# OPAMP_DEV_SOT5_6-23.net
KiCad netlist of a schematic drawn in Altium Designer
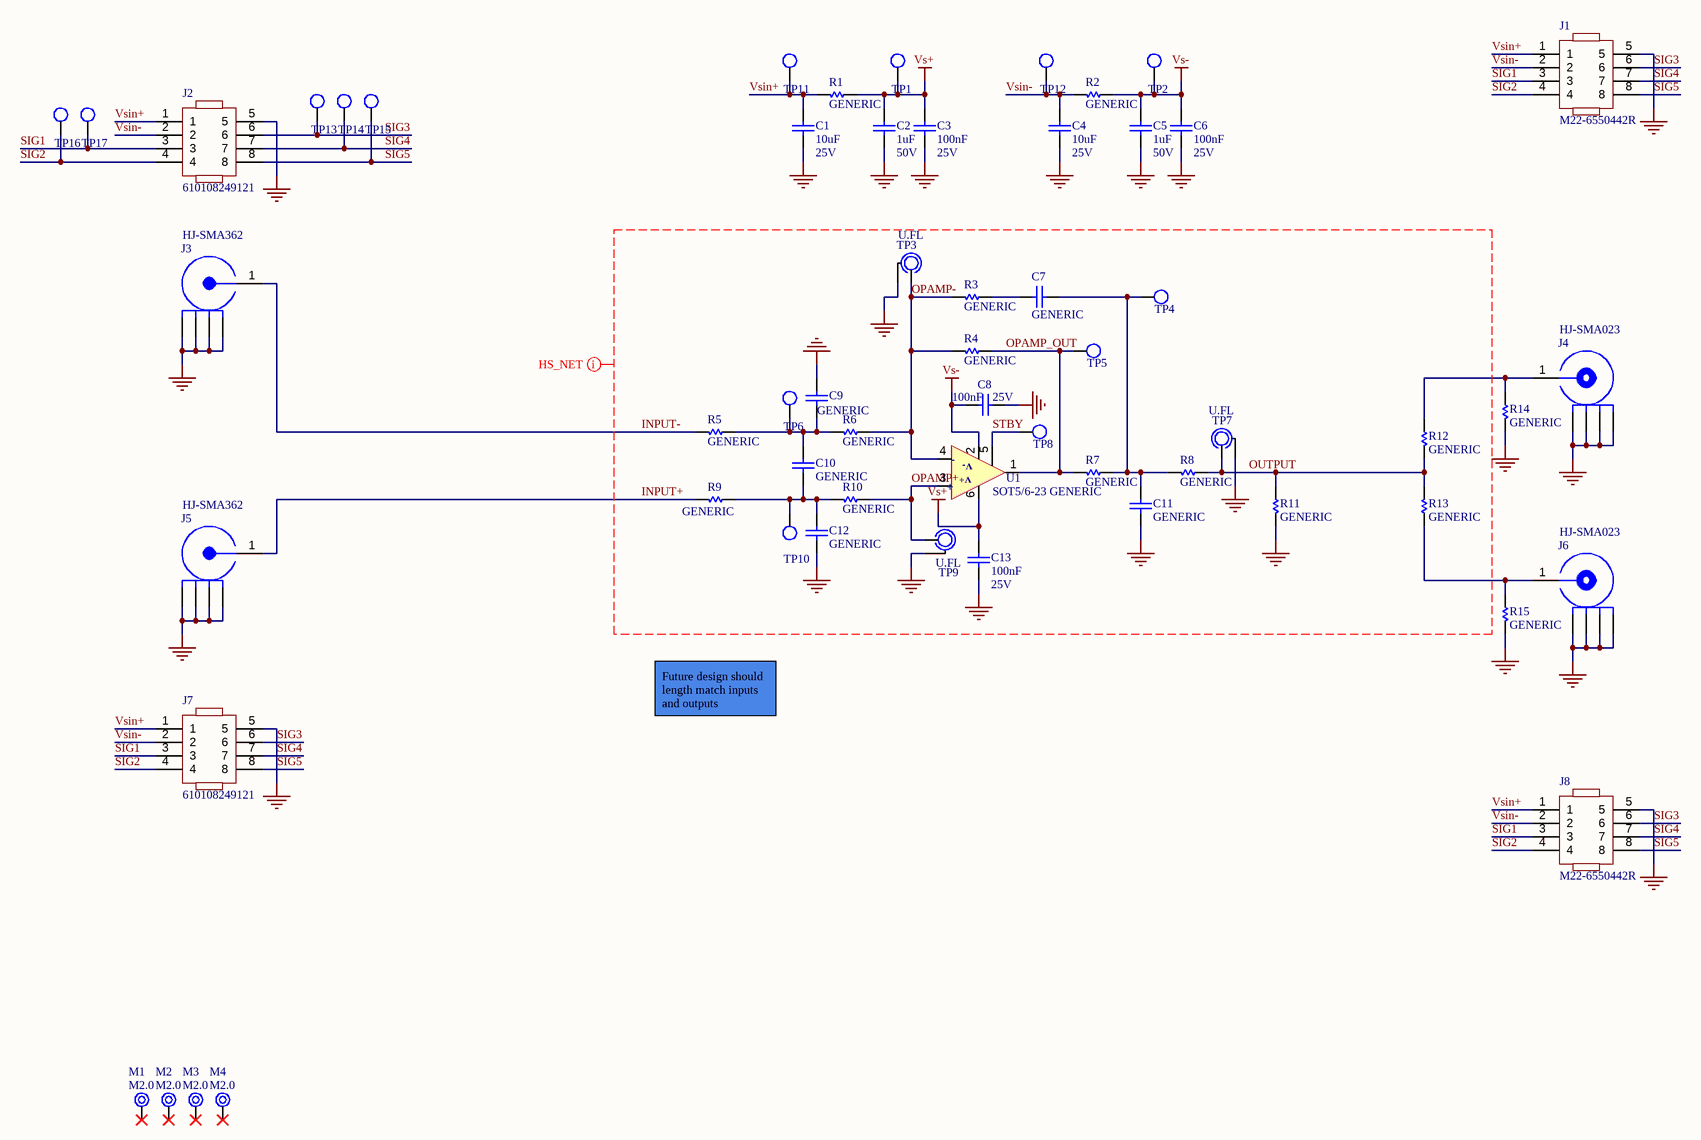
[diagram p0: OPAMP_DEV_SOT5_6-23.SchDoc]

(export (version "E")
  (design (tool "Eeschema 10.0.6"))
  (components
    (comp (ref "C1")
      (value "10uF")
      (footprint "c0805")
      (description "Cap Ceramic 10uF 25V X5R 10% SMD 0805 85°C Embossed T/R")
      (fields
        (field (name "MANUFACTURER") "Samsung")
        (field (name "MANUFACTURER PART NUMBER") "CL21A106KAYNNNE")
        (field (name "VOLTAGE RATING") "25V")
      )
      (libsource (lib "OPAMP_DEV_SOT5_6-23") (part "CAP CER 10uF 25V X5R 0805"))
    )
    (comp (ref "C2")
      (value "1uF")
      (footprint "c0603")
      (description "Multilayer Ceramic Capacitors (High dielectric type), 50V, 1 uF, ± 10 %, 0603, X5R, RoHS")
      (fields
        (field (name "MANUFACTURER") "Taiyo Yuden")
        (field (name "MANUFACTURER PART NUMBER") "UMK107BJ105KA-T")
        (field (name "VOLTAGE RATING") "50V")
      )
      (libsource (lib "OPAMP_DEV_SOT5_6-23") (part "CAP CER 1uF 50V X5R 0603"))
    )
    (comp (ref "C3")
      (value "100nF")
      (footprint "C0402")
      (description "Cap Ceramic 0.1uF 25V X5R 10% Pad SMD 0402 85°C T/R / Multi Layer Ceramic Capacitor (MLCC)")
      (fields
        (field (name "MANUFACTURER") "Samsung")
        (field (name "MANUFACTURER PART NUMBER") "CL05A104KA5NNNC")
        (field (name "VOLTAGE RATING") "25V")
      )
      (libsource (lib "OPAMP_DEV_SOT5_6-23") (part "CAP CER 100nF 25V X5R 0402"))
    )
    (comp (ref "C4")
      (value "10uF")
      (footprint "c0805")
      (description "Cap Ceramic 10uF 25V X5R 10% SMD 0805 85°C Embossed T/R")
      (fields
        (field (name "MANUFACTURER") "Samsung")
        (field (name "MANUFACTURER PART NUMBER") "CL21A106KAYNNNE")
        (field (name "VOLTAGE RATING") "25V")
      )
      (libsource (lib "OPAMP_DEV_SOT5_6-23") (part "CAP CER 10uF 25V X5R 0805"))
    )
    (comp (ref "C5")
      (value "1uF")
      (footprint "c0603")
      (description "Multilayer Ceramic Capacitors (High dielectric type), 50V, 1 uF, ± 10 %, 0603, X5R, RoHS")
      (fields
        (field (name "MANUFACTURER") "Taiyo Yuden")
        (field (name "MANUFACTURER PART NUMBER") "UMK107BJ105KA-T")
        (field (name "VOLTAGE RATING") "50V")
      )
      (libsource (lib "OPAMP_DEV_SOT5_6-23") (part "CAP CER 1uF 50V X5R 0603"))
    )
    (comp (ref "C6")
      (value "100nF")
      (footprint "C0402")
      (description "Cap Ceramic 0.1uF 25V X5R 10% Pad SMD 0402 85°C T/R / Multi Layer Ceramic Capacitor (MLCC)")
      (fields
        (field (name "MANUFACTURER") "Samsung")
        (field (name "MANUFACTURER PART NUMBER") "CL05A104KA5NNNC")
        (field (name "VOLTAGE RATING") "25V")
      )
      (libsource (lib "OPAMP_DEV_SOT5_6-23") (part "CAP CER 100nF 25V X5R 0402"))
    )
    (comp (ref "C7")
      (value "GENERIC")
      (footprint "C0402")
      (libsource (lib "OPAMP_DEV_SOT5_6-23") (part "CAP GENERIC 0402"))
    )
    (comp (ref "C8")
      (value "100nF")
      (footprint "C0402")
      (description "Cap Ceramic 0.1uF 25V X5R 10% Pad SMD 0402 85°C T/R / Multi Layer Ceramic Capacitor (MLCC)")
      (fields
        (field (name "MANUFACTURER") "Samsung")
        (field (name "MANUFACTURER PART NUMBER") "CL05A104KA5NNNC")
        (field (name "VOLTAGE RATING") "25V")
      )
      (libsource (lib "OPAMP_DEV_SOT5_6-23") (part "CAP CER 100nF 25V X5R 0402"))
    )
    (comp (ref "C9")
      (value "GENERIC")
      (footprint "C0402")
      (libsource (lib "OPAMP_DEV_SOT5_6-23") (part "CAP GENERIC 0402"))
    )
    (comp (ref "C10")
      (value "GENERIC")
      (footprint "C0402")
      (libsource (lib "OPAMP_DEV_SOT5_6-23") (part "CAP GENERIC 0402"))
    )
    (comp (ref "C11")
      (value "GENERIC")
      (footprint "C0402")
      (libsource (lib "OPAMP_DEV_SOT5_6-23") (part "CAP GENERIC 0402"))
    )
    (comp (ref "C12")
      (value "GENERIC")
      (footprint "C0402")
      (libsource (lib "OPAMP_DEV_SOT5_6-23") (part "CAP GENERIC 0402"))
    )
    (comp (ref "C13")
      (value "100nF")
      (footprint "C0402")
      (description "Cap Ceramic 0.1uF 25V X5R 10% Pad SMD 0402 85°C T/R / Multi Layer Ceramic Capacitor (MLCC)")
      (fields
        (field (name "MANUFACTURER") "Samsung")
        (field (name "MANUFACTURER PART NUMBER") "CL05A104KA5NNNC")
        (field (name "VOLTAGE RATING") "25V")
      )
      (libsource (lib "OPAMP_DEV_SOT5_6-23") (part "CAP CER 100nF 25V X5R 0402"))
    )
    (comp (ref "J1")
      (value "M22-6550442R")
      (footprint "CONN HDR 08 FEMALE RA 2ROW")
      (description "Conn Socket Strip RCP 8 POS 2mm Solder RA SMD T/R")
      (fields (field (name "MANUFACTURER") "Harwin"))
      (libsource (lib "OPAMP_DEV_SOT5_6-23") (part "CONN HDR 08 FEMALE RA 2 ROW"))
    )
    (comp (ref "J2")
      (value "610108249121")
      (footprint "CONN HDR 08 MALE RA 2ROW - duplicate")
      (description "SMT Angled Pin Header WR-PHD, Pitch 2.54 mm, Dual Row, 8 pins")
      (fields (field (name "MANUFACTURER") "Wurth Electronics"))
      (libsource (lib "OPAMP_DEV_SOT5_6-23") (part "CONN HDR 08 MALE RA 2 ROW"))
    )
    (comp (ref "J3")
      (value "HJ-SMA362")
      (footprint "SMA SMD PIN BRD EDGE")
      (libsource (lib "OPAMP_DEV_SOT5_6-23") (part "CON SMA PIN SMD BRD EDGE HJ-SMA362"))
    )
    (comp (ref "J4")
      (value "HJ-SMA023")
      (footprint "SMA SMD BORE BRD EDGE")
      (libsource (lib "OPAMP_DEV_SOT5_6-23") (part "CON SMA BORE SMD BRD EDGE HJ-SMA023"))
    )
    (comp (ref "J5")
      (value "HJ-SMA362")
      (footprint "SMA SMD PIN BRD EDGE")
      (libsource (lib "OPAMP_DEV_SOT5_6-23") (part "CON SMA PIN SMD BRD EDGE HJ-SMA362"))
    )
    (comp (ref "J6")
      (value "HJ-SMA023")
      (footprint "SMA SMD BORE BRD EDGE")
      (libsource (lib "OPAMP_DEV_SOT5_6-23") (part "CON SMA BORE SMD BRD EDGE HJ-SMA023"))
    )
    (comp (ref "J7")
      (value "610108249121")
      (footprint "CONN HDR 08 MALE RA 2ROW - duplicate")
      (description "SMT Angled Pin Header WR-PHD, Pitch 2.54 mm, Dual Row, 8 pins")
      (fields (field (name "MANUFACTURER") "Wurth Electronics"))
      (libsource (lib "OPAMP_DEV_SOT5_6-23") (part "CONN HDR 08 MALE RA 2 ROW"))
    )
    (comp (ref "J8")
      (value "M22-6550442R")
      (footprint "CONN HDR 08 FEMALE RA 2ROW")
      (description "Conn Socket Strip RCP 8 POS 2mm Solder RA SMD T/R")
      (fields (field (name "MANUFACTURER") "Harwin"))
      (libsource (lib "OPAMP_DEV_SOT5_6-23") (part "CONN HDR 08 FEMALE RA 2 ROW"))
    )
    (comp (ref "M1")
      (value "M2.0")
      (footprint "MECH M2.0 UNPLATED")
      (libsource (lib "OPAMP_DEV_SOT5_6-23") (part "MECH M2.0 UNPLATED"))
    )
    (comp (ref "M2")
      (value "M2.0")
      (footprint "MECH M2.0 UNPLATED")
      (libsource (lib "OPAMP_DEV_SOT5_6-23") (part "MECH M2.0 UNPLATED"))
    )
    (comp (ref "M3")
      (value "M2.0")
      (footprint "MECH M2.0 UNPLATED")
      (libsource (lib "OPAMP_DEV_SOT5_6-23") (part "MECH M2.0 UNPLATED"))
    )
    (comp (ref "M4")
      (value "M2.0")
      (footprint "MECH M2.0 UNPLATED")
      (libsource (lib "OPAMP_DEV_SOT5_6-23") (part "MECH M2.0 UNPLATED"))
    )
    (comp (ref "R1")
      (value "GENERIC")
      (footprint "R0603")
      (libsource (lib "OPAMP_DEV_SOT5_6-23") (part "RES GENERIC 0603"))
    )
    (comp (ref "R2")
      (value "GENERIC")
      (footprint "R0603")
      (libsource (lib "OPAMP_DEV_SOT5_6-23") (part "RES GENERIC 0603"))
    )
    (comp (ref "R3")
      (value "GENERIC")
      (footprint "R0402")
      (libsource (lib "OPAMP_DEV_SOT5_6-23") (part "RES GENERIC 0402"))
    )
    (comp (ref "R4")
      (value "GENERIC")
      (footprint "R0402")
      (libsource (lib "OPAMP_DEV_SOT5_6-23") (part "RES GENERIC 0402"))
    )
    (comp (ref "R5")
      (value "GENERIC")
      (footprint "R0402")
      (libsource (lib "OPAMP_DEV_SOT5_6-23") (part "RES GENERIC 0402"))
    )
    (comp (ref "R6")
      (value "GENERIC")
      (footprint "R0402")
      (libsource (lib "OPAMP_DEV_SOT5_6-23") (part "RES GENERIC 0402"))
    )
    (comp (ref "R7")
      (value "GENERIC")
      (footprint "R0402")
      (libsource (lib "OPAMP_DEV_SOT5_6-23") (part "RES GENERIC 0402"))
    )
    (comp (ref "R8")
      (value "GENERIC")
      (footprint "R0402")
      (libsource (lib "OPAMP_DEV_SOT5_6-23") (part "RES GENERIC 0402"))
    )
    (comp (ref "R9")
      (value "GENERIC")
      (footprint "R0402")
      (libsource (lib "OPAMP_DEV_SOT5_6-23") (part "RES GENERIC 0402"))
    )
    (comp (ref "R10")
      (value "GENERIC")
      (footprint "R0402")
      (libsource (lib "OPAMP_DEV_SOT5_6-23") (part "RES GENERIC 0402"))
    )
    (comp (ref "R11")
      (value "GENERIC")
      (footprint "R0402")
      (libsource (lib "OPAMP_DEV_SOT5_6-23") (part "RES GENERIC 0402"))
    )
    (comp (ref "R12")
      (value "GENERIC")
      (footprint "R0402")
      (libsource (lib "OPAMP_DEV_SOT5_6-23") (part "RES GENERIC 0402"))
    )
    (comp (ref "R13")
      (value "GENERIC")
      (footprint "R0402")
      (libsource (lib "OPAMP_DEV_SOT5_6-23") (part "RES GENERIC 0402"))
    )
    (comp (ref "R14")
      (value "GENERIC")
      (footprint "R0402")
      (libsource (lib "OPAMP_DEV_SOT5_6-23") (part "RES GENERIC 0402"))
    )
    (comp (ref "R15")
      (value "GENERIC")
      (footprint "R0402")
      (libsource (lib "OPAMP_DEV_SOT5_6-23") (part "RES GENERIC 0402"))
    )
    (comp (ref "TP1")
      (value "1mm")
      (footprint "TESTPOINT_SMT")
      (description "SMT testpoint")
      (libsource (lib "OPAMP_DEV_SOT5_6-23") (part "TP 1mm"))
    )
    (comp (ref "TP2")
      (value "1mm")
      (footprint "TESTPOINT_SMT")
      (description "SMT testpoint")
      (libsource (lib "OPAMP_DEV_SOT5_6-23") (part "TP 1mm"))
    )
    (comp (ref "TP3")
      (value "U.FL")
      (footprint "U.FL")
      (description "CONN U.FL RCPT STR 50 OHM SMD")
      (fields
        (field (name "MANUFACTURER") "Hirose")
        (field (name "MANUFACTURER PART NUMBER") "U.FL-R-SMT-1(80)")
      )
      (libsource (lib "") (part "TP U.FL_1"))
    )
    (comp (ref "TP4")
      (value "1mm")
      (footprint "TESTPOINT_SMT")
      (description "SMT testpoint")
      (libsource (lib "OPAMP_DEV_SOT5_6-23") (part "TP 1mm"))
    )
    (comp (ref "TP5")
      (value "1mm")
      (footprint "TESTPOINT_SMT")
      (description "SMT testpoint")
      (libsource (lib "OPAMP_DEV_SOT5_6-23") (part "TP 1mm"))
    )
    (comp (ref "TP6")
      (value "1mm")
      (footprint "TESTPOINT_SMT")
      (description "SMT testpoint")
      (libsource (lib "OPAMP_DEV_SOT5_6-23") (part "TP 1mm"))
    )
    (comp (ref "TP7")
      (value "U.FL")
      (footprint "U.FL")
      (description "CONN U.FL RCPT STR 50 OHM SMD")
      (fields
        (field (name "MANUFACTURER") "Hirose")
        (field (name "MANUFACTURER PART NUMBER") "U.FL-R-SMT-1(80)")
      )
      (libsource (lib "OPAMP_DEV_SOT5_6-23") (part "TP U.FL"))
    )
    (comp (ref "TP8")
      (value "1mm")
      (footprint "TESTPOINT_SMT")
      (description "SMT testpoint")
      (libsource (lib "OPAMP_DEV_SOT5_6-23") (part "TP 1mm"))
    )
    (comp (ref "TP9")
      (value "U.FL")
      (footprint "U.FL")
      (description "CONN U.FL RCPT STR 50 OHM SMD")
      (fields
        (field (name "MANUFACTURER") "Hirose")
        (field (name "MANUFACTURER PART NUMBER") "U.FL-R-SMT-1(80)")
      )
      (libsource (lib "OPAMP_DEV_SOT5_6-23") (part "TP U.FL"))
    )
    (comp (ref "TP10")
      (value "1mm")
      (footprint "TESTPOINT_SMT")
      (description "SMT testpoint")
      (libsource (lib "OPAMP_DEV_SOT5_6-23") (part "TP 1mm"))
    )
    (comp (ref "TP11")
      (value "1mm")
      (footprint "TESTPOINT_SMT")
      (description "SMT testpoint")
      (libsource (lib "OPAMP_DEV_SOT5_6-23") (part "TP 1mm"))
    )
    (comp (ref "TP12")
      (value "1mm")
      (footprint "TESTPOINT_SMT")
      (description "SMT testpoint")
      (libsource (lib "OPAMP_DEV_SOT5_6-23") (part "TP 1mm"))
    )
    (comp (ref "TP13")
      (value "1mm")
      (footprint "TESTPOINT_SMT")
      (description "SMT testpoint")
      (libsource (lib "OPAMP_DEV_SOT5_6-23") (part "TP 1mm"))
    )
    (comp (ref "TP14")
      (value "1mm")
      (footprint "TESTPOINT_SMT")
      (description "SMT testpoint")
      (libsource (lib "OPAMP_DEV_SOT5_6-23") (part "TP 1mm"))
    )
    (comp (ref "TP15")
      (value "1mm")
      (footprint "TESTPOINT_SMT")
      (description "SMT testpoint")
      (libsource (lib "OPAMP_DEV_SOT5_6-23") (part "TP 1mm"))
    )
    (comp (ref "TP16")
      (value "1mm")
      (footprint "TESTPOINT_SMT")
      (description "SMT testpoint")
      (libsource (lib "OPAMP_DEV_SOT5_6-23") (part "TP 1mm"))
    )
    (comp (ref "TP17")
      (value "1mm")
      (footprint "TESTPOINT_SMT")
      (description "SMT testpoint")
      (libsource (lib "OPAMP_DEV_SOT5_6-23") (part "TP 1mm"))
    )
    (comp (ref "U1")
      (value "SOT5/6-23 GENERIC")
      (footprint "SOT23-5/6_Modified")
      (libsource (lib "OPAMP_DEV_SOT5_6-23") (part "IC OPAMP SOT5/6-23 GENERIC"))
    )
  )
  (nets
    (net (code "1") (name "/INPUT+") (class "Default")
      (node (ref "J5") (pin "1") (pinfunction "1_1") (pintype "passive"))
      (node (ref "R9") (pin "2") (pinfunction "2_2") (pintype "passive"))
    )
    (net (code "2") (name "/INPUT-") (class "Default")
      (node (ref "J3") (pin "1") (pinfunction "1_1") (pintype "passive"))
      (node (ref "R5") (pin "2") (pinfunction "2_2") (pintype "passive"))
    )
    (net (code "3") (name "/OPAMP+") (class "Default")
      (node (ref "R10") (pin "1") (pinfunction "1_1") (pintype "passive"))
      (node (ref "TP9") (pin "1") (pinfunction "1_1") (pintype "passive"))
      (node (ref "U1") (pin "3") (pinfunction "+_3") (pintype "passive"))
    )
    (net (code "4") (name "/OPAMP-") (class "Default")
      (node (ref "R3") (pin "2") (pinfunction "2_2") (pintype "passive"))
      (node (ref "R4") (pin "2") (pinfunction "2_2") (pintype "passive"))
      (node (ref "R6") (pin "1") (pinfunction "1_1") (pintype "passive"))
      (node (ref "TP3") (pin "1") (pinfunction "1_1") (pintype "passive"))
      (node (ref "U1") (pin "4") (pinfunction "-_4") (pintype "passive"))
    )
    (net (code "5") (name "/OPAMP_OUT") (class "Default")
      (node (ref "R4") (pin "1") (pinfunction "1_1") (pintype "passive"))
      (node (ref "R7") (pin "2") (pinfunction "2_2") (pintype "passive"))
      (node (ref "TP5") (pin "1") (pinfunction "1_1") (pintype "passive"))
      (node (ref "U1") (pin "1") (pinfunction "1_1") (pintype "passive"))
    )
    (net (code "6") (name "/OUTPUT") (class "Default")
      (node (ref "R11") (pin "1") (pinfunction "1_1") (pintype "passive"))
      (node (ref "R12") (pin "2") (pinfunction "2_2") (pintype "passive"))
      (node (ref "R13") (pin "2") (pinfunction "2_2") (pintype "passive"))
      (node (ref "R8") (pin "1") (pinfunction "1_1") (pintype "passive"))
      (node (ref "TP7") (pin "1") (pinfunction "1_1") (pintype "passive"))
    )
    (net (code "7") (name "/SIG1") (class "Default")
      (node (ref "J1") (pin "3") (pinfunction "3_3") (pintype "passive"))
      (node (ref "J2") (pin "3") (pinfunction "3_3") (pintype "passive"))
      (node (ref "J7") (pin "3") (pinfunction "3_3") (pintype "passive"))
      (node (ref "J8") (pin "3") (pinfunction "3_3") (pintype "passive"))
      (node (ref "TP17") (pin "1") (pinfunction "1_1") (pintype "passive"))
    )
    (net (code "8") (name "/SIG2") (class "Default")
      (node (ref "J1") (pin "4") (pinfunction "4_4") (pintype "passive"))
      (node (ref "J2") (pin "4") (pinfunction "4_4") (pintype "passive"))
      (node (ref "J7") (pin "4") (pinfunction "4_4") (pintype "passive"))
      (node (ref "J8") (pin "4") (pinfunction "4_4") (pintype "passive"))
      (node (ref "TP16") (pin "1") (pinfunction "1_1") (pintype "passive"))
    )
    (net (code "9") (name "/SIG3") (class "Default")
      (node (ref "J1") (pin "6") (pinfunction "6_6") (pintype "passive"))
      (node (ref "J2") (pin "6") (pinfunction "6_6") (pintype "passive"))
      (node (ref "J7") (pin "6") (pinfunction "6_6") (pintype "passive"))
      (node (ref "J8") (pin "6") (pinfunction "6_6") (pintype "passive"))
      (node (ref "TP13") (pin "1") (pinfunction "1_1") (pintype "passive"))
    )
    (net (code "10") (name "/SIG4") (class "Default")
      (node (ref "J1") (pin "7") (pinfunction "7_7") (pintype "passive"))
      (node (ref "J2") (pin "7") (pinfunction "7_7") (pintype "passive"))
      (node (ref "J7") (pin "7") (pinfunction "7_7") (pintype "passive"))
      (node (ref "J8") (pin "7") (pinfunction "7_7") (pintype "passive"))
      (node (ref "TP14") (pin "1") (pinfunction "1_1") (pintype "passive"))
    )
    (net (code "11") (name "/SIG5") (class "Default")
      (node (ref "J1") (pin "8") (pinfunction "8_8") (pintype "passive"))
      (node (ref "J2") (pin "8") (pinfunction "8_8") (pintype "passive"))
      (node (ref "J7") (pin "8") (pinfunction "8_8") (pintype "passive"))
      (node (ref "J8") (pin "8") (pinfunction "8_8") (pintype "passive"))
      (node (ref "TP15") (pin "1") (pinfunction "1_1") (pintype "passive"))
    )
    (net (code "12") (name "/STBY") (class "Default")
      (node (ref "TP8") (pin "1") (pinfunction "1_1") (pintype "passive"))
      (node (ref "U1") (pin "5") (pinfunction "1_5") (pintype "passive"))
    )
    (net (code "13") (name "/Vsin+") (class "Default")
      (node (ref "C1") (pin "2") (pinfunction "2_2") (pintype "passive"))
      (node (ref "J1") (pin "1") (pinfunction "1_1") (pintype "passive"))
      (node (ref "J2") (pin "1") (pinfunction "1_1") (pintype "passive"))
      (node (ref "J7") (pin "1") (pinfunction "1_1") (pintype "passive"))
      (node (ref "J8") (pin "1") (pinfunction "1_1") (pintype "passive"))
      (node (ref "R1") (pin "2") (pinfunction "2_2") (pintype "passive"))
      (node (ref "TP11") (pin "1") (pinfunction "1_1") (pintype "passive"))
    )
    (net (code "14") (name "/Vsin-") (class "Default")
      (node (ref "C4") (pin "2") (pinfunction "2_2") (pintype "passive"))
      (node (ref "J1") (pin "2") (pinfunction "2_2") (pintype "passive"))
      (node (ref "J2") (pin "2") (pinfunction "2_2") (pintype "passive"))
      (node (ref "J7") (pin "2") (pinfunction "2_2") (pintype "passive"))
      (node (ref "J8") (pin "2") (pinfunction "2_2") (pintype "passive"))
      (node (ref "R2") (pin "2") (pinfunction "2_2") (pintype "passive"))
      (node (ref "TP12") (pin "1") (pinfunction "1_1") (pintype "passive"))
    )
    (net (code "15") (name "GND") (class "Default")
      (node (ref "C1") (pin "1") (pinfunction "1_1") (pintype "passive"))
      (node (ref "C11") (pin "1") (pinfunction "1_1") (pintype "passive"))
      (node (ref "C12") (pin "1") (pinfunction "1_1") (pintype "passive"))
      (node (ref "C13") (pin "2") (pinfunction "2_2") (pintype "passive"))
      (node (ref "C2") (pin "1") (pinfunction "1_1") (pintype "passive"))
      (node (ref "C3") (pin "1") (pinfunction "1_1") (pintype "passive"))
      (node (ref "C4") (pin "1") (pinfunction "1_1") (pintype "passive"))
      (node (ref "C5") (pin "1") (pinfunction "1_1") (pintype "passive"))
      (node (ref "C6") (pin "1") (pinfunction "1_1") (pintype "passive"))
      (node (ref "C8") (pin "2") (pinfunction "2_2") (pintype "passive"))
      (node (ref "C9") (pin "2") (pinfunction "2_2") (pintype "passive"))
      (node (ref "J1") (pin "5") (pinfunction "5_5") (pintype "passive"))
      (node (ref "J2") (pin "5") (pinfunction "5_5") (pintype "passive"))
      (node (ref "J3") (pin "0") (pinfunction "5_0") (pintype "passive"))
      (node (ref "J4") (pin "0") (pinfunction "2_0") (pintype "passive"))
      (node (ref "J5") (pin "0") (pinfunction "2_0") (pintype "passive"))
      (node (ref "J6") (pin "0") (pinfunction "5_0") (pintype "passive"))
      (node (ref "J7") (pin "5") (pinfunction "5_5") (pintype "passive"))
      (node (ref "J8") (pin "5") (pinfunction "5_5") (pintype "passive"))
      (node (ref "R11") (pin "2") (pinfunction "2_2") (pintype "passive"))
      (node (ref "R14") (pin "2") (pinfunction "2_2") (pintype "passive"))
      (node (ref "R15") (pin "2") (pinfunction "2_2") (pintype "passive"))
      (node (ref "TP3") (pin "0") (pinfunction "0_0") (pintype "passive"))
      (node (ref "TP7") (pin "0") (pinfunction "0_0") (pintype "passive"))
      (node (ref "TP9") (pin "0") (pinfunction "0_0") (pintype "passive"))
    )
    (net (code "16") (name "Net-(C7-Pad2)") (class "Default")
      (node (ref "C7") (pin "2") (pinfunction "2_2") (pintype "passive"))
      (node (ref "R3") (pin "1") (pinfunction "1_1") (pintype "passive"))
    )
    (net (code "17") (name "Net-(C10-Pad1)") (class "Default")
      (node (ref "C10") (pin "1") (pinfunction "1_1") (pintype "passive"))
      (node (ref "C12") (pin "2") (pinfunction "2_2") (pintype "passive"))
      (node (ref "R10") (pin "2") (pinfunction "2_2") (pintype "passive"))
      (node (ref "R9") (pin "1") (pinfunction "1_1") (pintype "passive"))
      (node (ref "TP10") (pin "1") (pinfunction "1_1") (pintype "passive"))
    )
    (net (code "18") (name "Net-(C10-Pad2)") (class "Default")
      (node (ref "C10") (pin "2") (pinfunction "2_2") (pintype "passive"))
      (node (ref "C9") (pin "1") (pinfunction "1_1") (pintype "passive"))
      (node (ref "R5") (pin "1") (pinfunction "1_1") (pintype "passive"))
      (node (ref "R6") (pin "2") (pinfunction "2_2") (pintype "passive"))
      (node (ref "TP6") (pin "1") (pinfunction "1_1") (pintype "passive"))
    )
    (net (code "19") (name "Net-(C11-Pad2)") (class "Default")
      (node (ref "C11") (pin "2") (pinfunction "2_2") (pintype "passive"))
      (node (ref "C7") (pin "1") (pinfunction "1_1") (pintype "passive"))
      (node (ref "R7") (pin "1") (pinfunction "1_1") (pintype "passive"))
      (node (ref "R8") (pin "2") (pinfunction "2_2") (pintype "passive"))
      (node (ref "TP4") (pin "1") (pinfunction "1_1") (pintype "passive"))
    )
    (net (code "20") (name "Net-(J4-Pad1)") (class "Default")
      (node (ref "J4") (pin "1") (pinfunction "1_1") (pintype "passive"))
      (node (ref "R12") (pin "1") (pinfunction "1_1") (pintype "passive"))
      (node (ref "R14") (pin "1") (pinfunction "1_1") (pintype "passive"))
    )
    (net (code "21") (name "Net-(J6-Pad1)") (class "Default")
      (node (ref "J6") (pin "1") (pinfunction "1_1") (pintype "passive"))
      (node (ref "R13") (pin "1") (pinfunction "1_1") (pintype "passive"))
      (node (ref "R15") (pin "1") (pinfunction "1_1") (pintype "passive"))
    )
    (net (code "22") (name "Vs+") (class "Default")
      (node (ref "C13") (pin "1") (pinfunction "1_1") (pintype "passive"))
      (node (ref "C2") (pin "2") (pinfunction "2_2") (pintype "passive"))
      (node (ref "C3") (pin "2") (pinfunction "2_2") (pintype "passive"))
      (node (ref "R1") (pin "1") (pinfunction "1_1") (pintype "passive"))
      (node (ref "TP1") (pin "1") (pinfunction "1_1") (pintype "passive"))
      (node (ref "U1") (pin "6") (pinfunction "V+_6") (pintype "passive"))
    )
    (net (code "23") (name "Vs-") (class "Default")
      (node (ref "C5") (pin "2") (pinfunction "2_2") (pintype "passive"))
      (node (ref "C6") (pin "2") (pinfunction "2_2") (pintype "passive"))
      (node (ref "C8") (pin "1") (pinfunction "1_1") (pintype "passive"))
      (node (ref "R2") (pin "1") (pinfunction "1_1") (pintype "passive"))
      (node (ref "TP2") (pin "1") (pinfunction "1_1") (pintype "passive"))
      (node (ref "U1") (pin "2") (pinfunction "V-_2") (pintype "passive"))
    )
    (net (code "24") (name "unconnected-(M1-Pad1)") (class "Default")
      (node (ref "M1") (pin "1") (pinfunction "1_1") (pintype "passive+no_connect"))
    )
    (net (code "25") (name "unconnected-(M2-Pad1)") (class "Default")
      (node (ref "M2") (pin "1") (pinfunction "1_1") (pintype "passive+no_connect"))
    )
    (net (code "26") (name "unconnected-(M3-Pad1)") (class "Default")
      (node (ref "M3") (pin "1") (pinfunction "1_1") (pintype "passive+no_connect"))
    )
    (net (code "27") (name "unconnected-(M4-Pad1)") (class "Default")
      (node (ref "M4") (pin "1") (pinfunction "1_1") (pintype "passive+no_connect"))
    )
  )
)
